# RLC_Demonstration.net
KiCad netlist of a schematic drawn in EAGLE
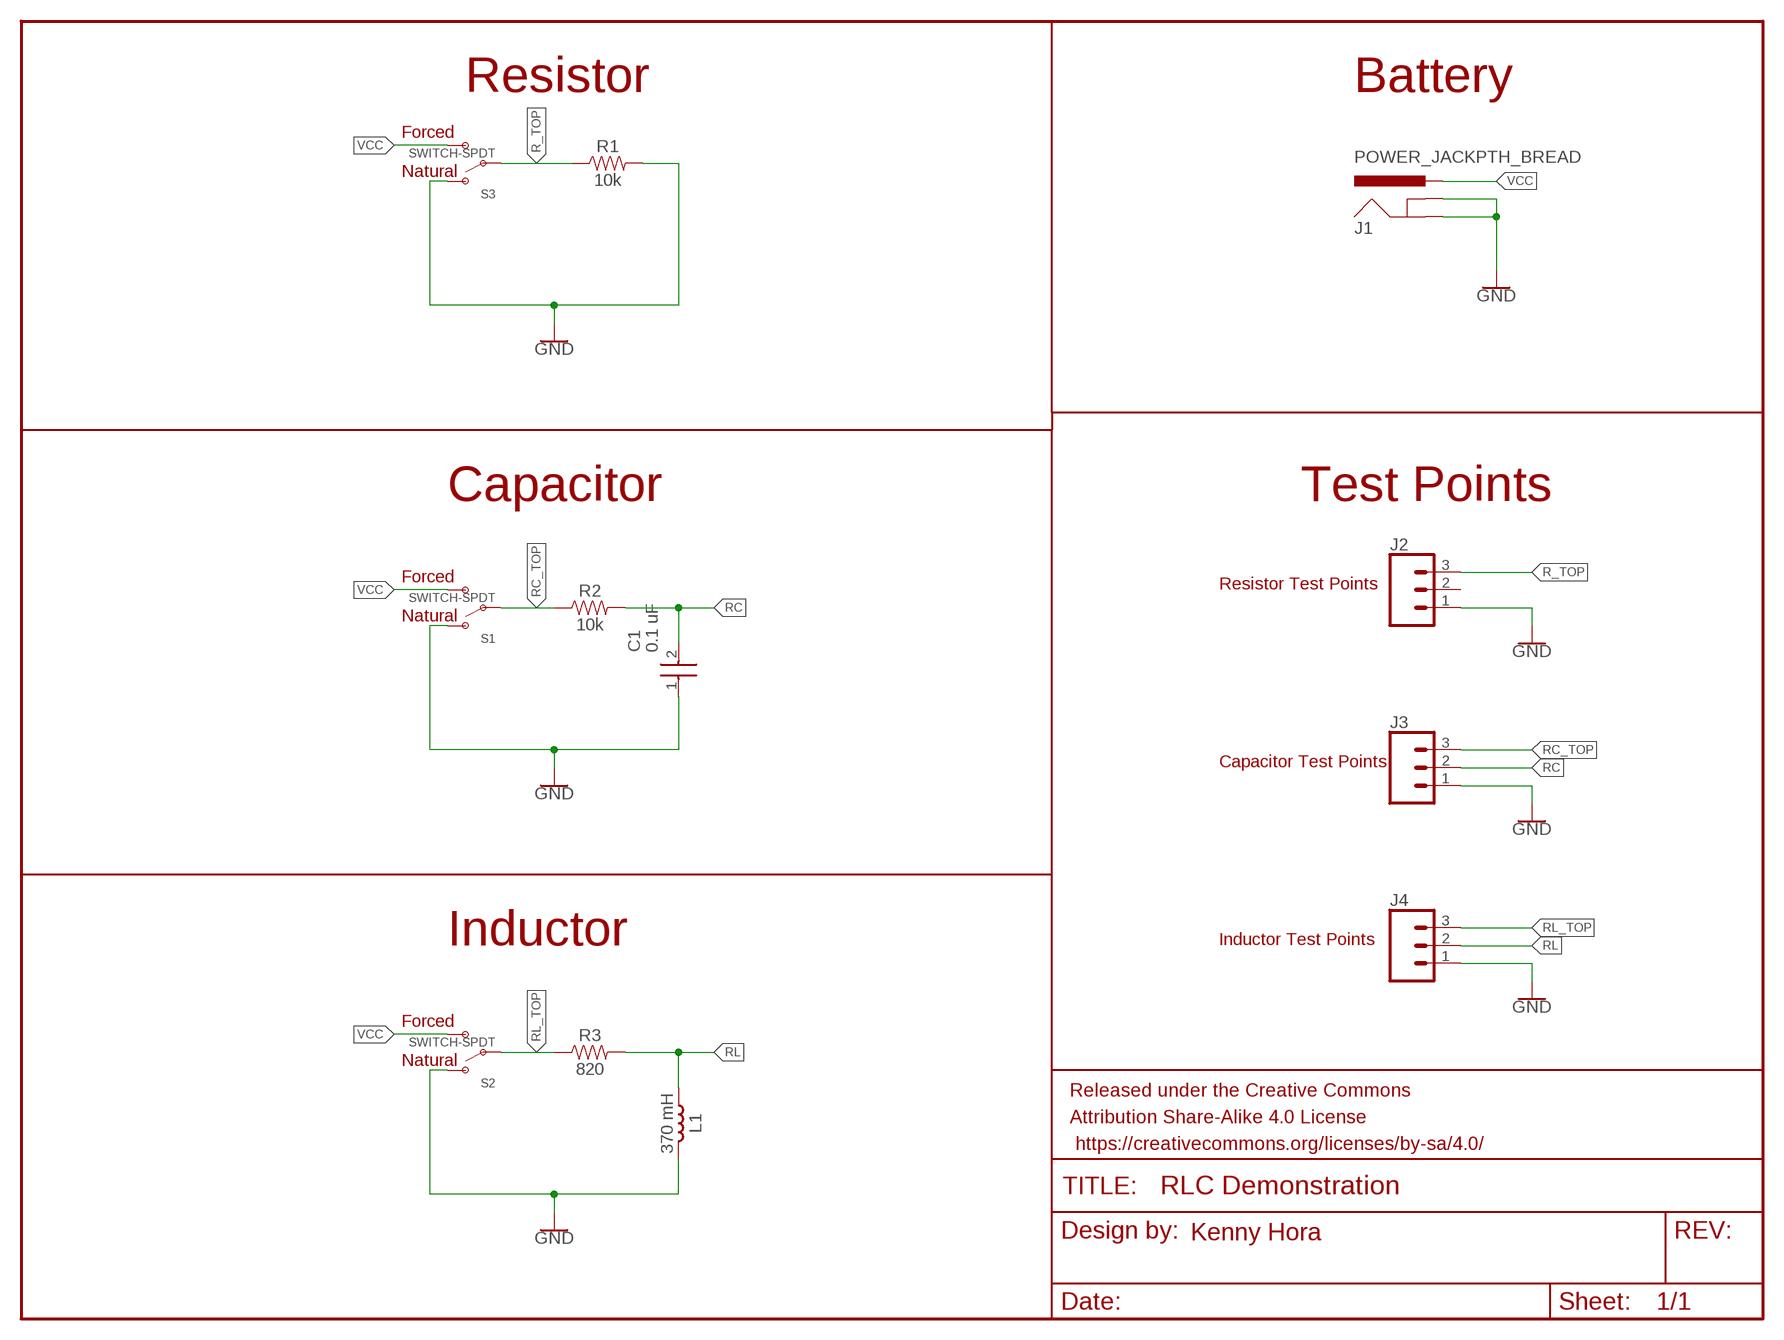
[diagram p0: schematic, sheet 1]

(export (version "E")
  (design (tool "Eeschema 10.0.6"))
  (components
    (comp (ref "C1")
      (value "0.1 uF")
      (footprint "eagle-import:K104K15X7RF53H5")
      (fields
        (field (name "ARROW_PART_NUMBER") "K104K15X7RF53H5")
        (field (name "MOUSER_PART_NUMBER") "594-K104K15X7RF53H5")
      )
      (libsource (lib "eagle-import") (part "K104K15X7RF53H5"))
    )
    (comp (ref "FRAME1")
      (value "FRAME-LETTERNO_PACKAGE")
      (footprint "eagle-import:DUMMY")
      (fields (field (name "DESIGNER") "Nobody"))
      (libsource (lib "eagle-import") (part "FRAME-LETTERNO_PACKAGE"))
    )
    (comp (ref "J1")
      (value "POWER_JACKPTH_BREAD")
      (footprint "eagle-import:POWER_JACK_PTH_BREAD")
      (libsource (lib "eagle-import") (part "POWER_JACKPTH_BREAD"))
    )
    (comp (ref "J2")
      (value "CONN_03LOCK")
      (footprint "eagle-import:1X03_LOCK")
      (libsource (lib "eagle-import") (part "CONN_03LOCK"))
    )
    (comp (ref "J3")
      (value "CONN_03LOCK")
      (footprint "eagle-import:1X03_LOCK")
      (libsource (lib "eagle-import") (part "CONN_03LOCK"))
    )
    (comp (ref "J4")
      (value "CONN_03LOCK")
      (footprint "eagle-import:1X03_LOCK")
      (libsource (lib "eagle-import") (part "CONN_03LOCK"))
    )
    (comp (ref "L1")
      (value "370 mH")
      (footprint "eagle-import:KNOWLES-5100-253441")
      (libsource (lib "eagle-import") (part "KNOWLES-370MH-5100-253441"))
    )
    (comp (ref "R1")
      (value "10k")
      (footprint "eagle-import:AXIAL-0.3")
      (libsource (lib "eagle-import") (part "10KOHM-HORIZ-1/4W-5%"))
    )
    (comp (ref "R2")
      (value "10k")
      (footprint "eagle-import:AXIAL-0.3")
      (libsource (lib "eagle-import") (part "10KOHM-HORIZ-1/4W-5%"))
    )
    (comp (ref "R3")
      (value "820")
      (footprint "eagle-import:AXIAL-0.3")
      (libsource (lib "eagle-import") (part "10KOHM-HORIZ-1/4W-5%"))
    )
    (comp (ref "S1")
      (value "SWITCH-SPDT")
      (footprint "eagle-import:OS102011MA1QN1")
      (libsource (lib "eagle-import") (part "SWITCH-SPDT"))
    )
    (comp (ref "S2")
      (value "SWITCH-SPDT")
      (footprint "eagle-import:OS102011MA1QN1")
      (libsource (lib "eagle-import") (part "SWITCH-SPDT"))
    )
    (comp (ref "S3")
      (value "SWITCH-SPDT")
      (footprint "eagle-import:OS102011MA1QN1")
      (libsource (lib "eagle-import") (part "SWITCH-SPDT"))
    )
  )
  (nets
    (net (code "1") (name "GND") (class "Default")
      (node (ref "C1") (pin "1") (pinfunction "1_1") (pintype "bidirectional"))
      (node (ref "J1") (pin "GND") (pinfunction "GND_GND") (pintype "bidirectional"))
      (node (ref "J1") (pin "GNDBREAK") (pinfunction "GNDBREAK_GNDBREAK") (pintype "bidirectional"))
      (node (ref "J2") (pin "1") (pinfunction "1_1") (pintype "passive"))
      (node (ref "J3") (pin "1") (pinfunction "1_1") (pintype "passive"))
      (node (ref "J4") (pin "1") (pinfunction "1_1") (pintype "passive"))
      (node (ref "L1") (pin "P$1") (pinfunction "P$1_P$1") (pintype "bidirectional"))
      (node (ref "R1") (pin "P$2") (pinfunction "2_P$2") (pintype "passive"))
      (node (ref "S1") (pin "P$2") (pinfunction "P$2_P$2") (pintype "bidirectional"))
      (node (ref "S2") (pin "P$2") (pinfunction "P$2_P$2") (pintype "bidirectional"))
      (node (ref "S3") (pin "P$2") (pinfunction "P$2_P$2") (pintype "bidirectional"))
    )
    (net (code "2") (name "RC") (class "Default")
      (node (ref "C1") (pin "2") (pinfunction "2_2") (pintype "bidirectional"))
      (node (ref "J3") (pin "2") (pinfunction "2_2") (pintype "passive"))
      (node (ref "R2") (pin "P$2") (pinfunction "2_P$2") (pintype "passive"))
    )
    (net (code "3") (name "RC_TOP") (class "Default")
      (node (ref "J3") (pin "3") (pinfunction "3_3") (pintype "passive"))
      (node (ref "R2") (pin "P$1") (pinfunction "1_P$1") (pintype "passive"))
      (node (ref "S1") (pin "P$1") (pinfunction "P$1_P$1") (pintype "bidirectional"))
    )
    (net (code "4") (name "RL") (class "Default")
      (node (ref "J4") (pin "2") (pinfunction "2_2") (pintype "passive"))
      (node (ref "L1") (pin "P$2") (pinfunction "P$2_P$2") (pintype "bidirectional"))
      (node (ref "R3") (pin "P$2") (pinfunction "2_P$2") (pintype "passive"))
    )
    (net (code "5") (name "RL_TOP") (class "Default")
      (node (ref "J4") (pin "3") (pinfunction "3_3") (pintype "passive"))
      (node (ref "R3") (pin "P$1") (pinfunction "1_P$1") (pintype "passive"))
      (node (ref "S2") (pin "P$1") (pinfunction "P$1_P$1") (pintype "bidirectional"))
    )
    (net (code "6") (name "R_TOP") (class "Default")
      (node (ref "J2") (pin "3") (pinfunction "3_3") (pintype "passive"))
      (node (ref "R1") (pin "P$1") (pinfunction "1_P$1") (pintype "passive"))
      (node (ref "S3") (pin "P$1") (pinfunction "P$1_P$1") (pintype "bidirectional"))
    )
    (net (code "7") (name "VCC") (class "Default")
      (node (ref "J1") (pin "PWR") (pinfunction "PWR_PWR") (pintype "bidirectional"))
      (node (ref "S1") (pin "P$3") (pinfunction "P$3_P$3") (pintype "bidirectional"))
      (node (ref "S2") (pin "P$3") (pinfunction "P$3_P$3") (pintype "bidirectional"))
      (node (ref "S3") (pin "P$3") (pinfunction "P$3_P$3") (pintype "bidirectional"))
    )
    (net (code "8") (name "unconnected-(J2-Pad2)") (class "Default")
      (node (ref "J2") (pin "2") (pinfunction "2_2") (pintype "passive"))
    )
  )
)
